# Analog.net
KiCad netlist of a schematic drawn in Altium Designer
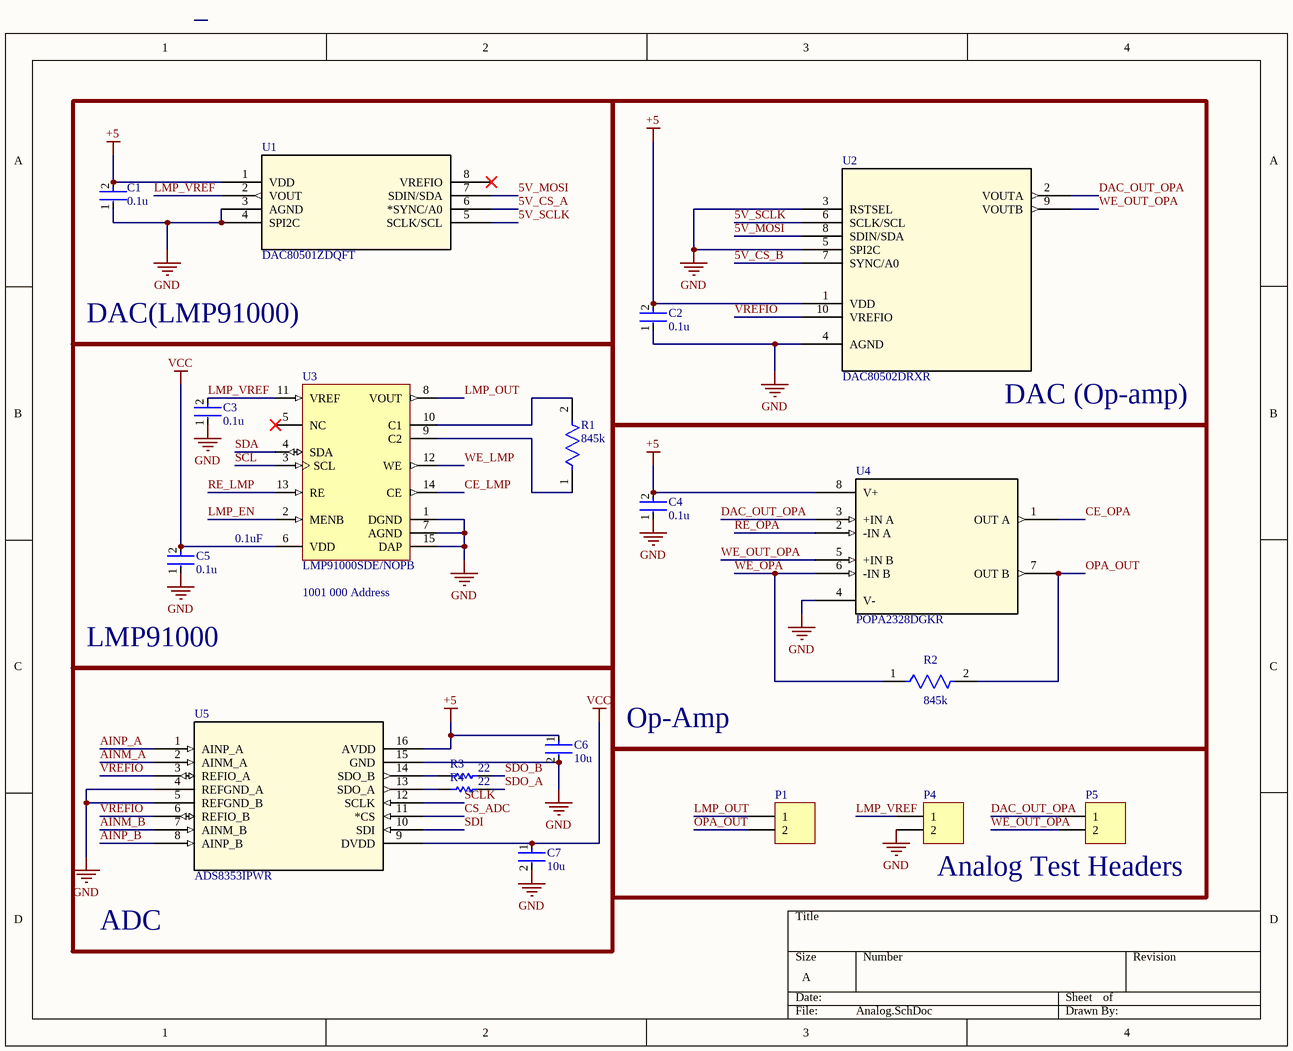
[diagram p0: Analog.SchDoc]

(export (version "E")
  (design (tool "Eeschema 10.0.6"))
  (components
    (comp (ref "C1")
      (value "0.1u")
      (footprint "FP-GCJ188-0_2-IPC_C")
      (description "Cap Ceramic 0.1uF 50V X7R 10% Pad SMD 0603 Soft Termination +125°C Automotive T/R")
      (fields (field (name "TOLERANCE") "10%"))
      (libsource (lib "Altium Content Vault") (part "f23184f103b6ebe33a8c269c53dcba6"))
    )
    (comp (ref "C2")
      (value "0.1u")
      (footprint "FP-GCJ188-0_2-IPC_C")
      (description "Cap Ceramic 0.1uF 50V X7R 10% Pad SMD 0603 Soft Termination +125°C Automotive T/R")
      (fields (field (name "TOLERANCE") "10%"))
      (libsource (lib "Altium Content Vault") (part "f23184f103b6ebe33a8c269c53dcba6"))
    )
    (comp (ref "C3")
      (value "0.1u")
      (footprint "FP-GCJ188-0_2-IPC_C")
      (description "Cap Ceramic 0.1uF 50V X7R 10% Pad SMD 0603 Soft Termination +125°C Automotive T/R")
      (fields (field (name "TOLERANCE") "10%"))
      (libsource (lib "Altium Content Vault") (part "f23184f103b6ebe33a8c269c53dcba6"))
    )
    (comp (ref "C4")
      (value "0.1u")
      (footprint "FP-GCJ188-0_2-IPC_C")
      (description "Cap Ceramic 0.1uF 50V X7R 10% Pad SMD 0603 Soft Termination +125°C Automotive T/R")
      (fields (field (name "TOLERANCE") "10%"))
      (libsource (lib "Altium Content Vault") (part "f23184f103b6ebe33a8c269c53dcba6"))
    )
    (comp (ref "C5")
      (value "0.1u")
      (footprint "FP-GCJ188-0_2-IPC_C")
      (description "Cap Ceramic 0.1uF 50V X7R 10% Pad SMD 0603 Soft Termination +125°C Automotive T/R")
      (fields (field (name "TOLERANCE") "10%"))
      (libsource (lib "Altium Content Vault") (part "f23184f103b6ebe33a8c269c53dcba6"))
    )
    (comp (ref "C6")
      (value "10u")
      (footprint "FP-CL21-IPC_C")
      (description "CL21 Series 0805 10uF 6.3V ±10% Tolerance X7R Multilayer Ceramic Chip Capacitor")
      (fields (field (name "TOLERANCE") "10%") (field (name "VOLTAGE") "6.3V"))
      (libsource (lib "Altium Content Vault") (part "b4654b650e69147ec39a6b967a45e02"))
    )
    (comp (ref "C7")
      (value "10u")
      (footprint "FP-CL21-IPC_C")
      (description "CL21 Series 0805 10uF 6.3V ±10% Tolerance X7R Multilayer Ceramic Chip Capacitor")
      (fields (field (name "TOLERANCE") "10%") (field (name "VOLTAGE") "6.3V"))
      (libsource (lib "Altium Content Vault") (part "b4654b650e69147ec39a6b967a45e02"))
    )
    (comp (ref "P1")
      (value "Header 2")
      (footprint "My_1X02")
      (description "Header, 2-Pin")
      (fields (field (name "ASID PART NUMBER") "Header 2-AS"))
      (libsource (lib "Mylib+Rev+4 (1)") (part "Header 2"))
    )
    (comp (ref "P4")
      (value "Header 2")
      (footprint "My_1X02")
      (description "Header, 2-Pin")
      (fields (field (name "ASID PART NUMBER") "Header 2-AS"))
      (libsource (lib "Mylib+Rev+4 (1)") (part "Header 2"))
    )
    (comp (ref "P5")
      (value "Header 2")
      (footprint "My_1X02")
      (description "Header, 2-Pin")
      (fields (field (name "ASID PART NUMBER") "Header 2-AS"))
      (libsource (lib "Mylib+Rev+4 (1)") (part "Header 2"))
    )
    (comp (ref "R1")
      (value "845k")
      (footprint "FP-CR0603-IPC_B")
      (description "Thick Film Chip Resistors 0603 845kΩ 0.1W 1% 100ppm/°C")
      (fields (field (name "TOLERANCE") "1%"))
      (libsource (lib "Altium Content Vault") (part "1029c3af85768c4190bb7ad29bc67b5"))
    )
    (comp (ref "R2")
      (value "845k")
      (footprint "FP-CR0603-IPC_B")
      (description "Thick Film Chip Resistors 0603 845kΩ 0.1W 1% 100ppm/°C")
      (fields (field (name "TOLERANCE") "1%"))
      (libsource (lib "Altium Content Vault") (part "1029c3af85768c4190bb7ad29bc67b5"))
    )
    (comp (ref "R3")
      (value "22")
      (footprint "RESC1608X55X25LL10T15")
      (fields (field (name "MANUFACTURER") "Yageo") (field (name "PART NUMBER") "RC0603FR-1022RL"))
      (libsource (lib "Altium Content Vault") (part "RES"))
    )
    (comp (ref "R4")
      (value "22")
      (footprint "RESC1608X55X25LL10T15")
      (fields (field (name "MANUFACTURER") "Yageo") (field (name "PART NUMBER") "RC0603FR-1022RL"))
      (libsource (lib "Altium Content Vault") (part "RES"))
    )
    (comp (ref "U1")
      (value "DAC80501ZDQFT")
      (footprint "WSON8_2P1X2P1_TEX")
      (description "True 16-bit, 1-ch, SPI/I2C, voltage-output DAC in WSON package with precision internal reference")
      (libsource (lib "DAC80501ZDQFT") (part "DAC80501ZDQFT"))
    )
    (comp (ref "U2")
      (value "DAC80502DRXR")
      (footprint "SON_02DRXR_TEX")
      (description "Dual-channel, 1-LSB INL, 16-bit, SPI voltage-output digital-to-analog converter (DAC)")
      (libsource (lib "DAC80502DRXR") (part "DAC80502DRXR"))
    )
    (comp (ref "U3")
      (value "LMP91000SDE/NOPB")
      (footprint "NHL0014B_V")
      (description "Configurable AFE Potentiostat for Low-Power Chemical Sensing Applications, 14-pin LLP, 250 Reel")
      (fields (field (name "MANUFACTURER") "Texas Instruments"))
      (libsource (lib "Altium Content Vault") (part "SEN-ELECHEM-LMP91000-15"))
    )
    (comp (ref "U4")
      (value "POPA2328DGKR")
      (footprint "SO8_DGK_TEX")
      (description "Dual-channel, precision, 50-µV offset voltage, 40-MHz wide-bandwidth RRIO CMOS op amp")
      (libsource (lib "POPA2328DGKR") (part "POPA2328DGKR"))
    )
    (comp (ref "U5")
      (value "ADS8353IPWR")
      (footprint "PW16_TEX")
      (description "16-bit 600-kSPS 2-channel simultaneous-sampling SAR ADC with single-ended inputs")
      (libsource (lib "ADS8353IPWR") (part "ADS8353IPWR"))
    )
  )
  (nets
    (net (code "1") (name "+5") (class "Default")
      (node (ref "C1") (pin "2") (pinfunction "2_2") (pintype "passive"))
      (node (ref "C2") (pin "2") (pinfunction "2_2") (pintype "passive"))
      (node (ref "C4") (pin "2") (pinfunction "2_2") (pintype "passive"))
      (node (ref "C6") (pin "1") (pinfunction "1_1") (pintype "passive"))
      (node (ref "U1") (pin "1") (pinfunction "VDD_1") (pintype "power_in"))
      (node (ref "U2") (pin "1") (pinfunction "VDD_1") (pintype "power_in"))
      (node (ref "U4") (pin "8") (pinfunction "V+_8") (pintype "power_in"))
      (node (ref "U5") (pin "16") (pinfunction "AVDD_16") (pintype "power_in"))
    )
    (net (code "2") (name "/5V_CS_A") (class "Default")
      (node (ref "U1") (pin "6") (pinfunction "*SYNC/A0_6") (pintype "passive"))
    )
    (net (code "3") (name "/5V_CS_B") (class "Default")
      (node (ref "U2") (pin "7") (pinfunction "SYNC/A0_7") (pintype "passive"))
    )
    (net (code "4") (name "/5V_MOSI") (class "Default")
      (node (ref "U1") (pin "7") (pinfunction "SDIN/SDA_7") (pintype "passive"))
      (node (ref "U2") (pin "8") (pinfunction "SDIN/SDA_8") (pintype "passive"))
    )
    (net (code "5") (name "/5V_SCLK") (class "Default")
      (node (ref "U1") (pin "5") (pinfunction "SCLK/SCL_5") (pintype "passive"))
      (node (ref "U2") (pin "6") (pinfunction "SCLK/SCL_6") (pintype "passive"))
    )
    (net (code "6") (name "/AINM_A") (class "Default")
      (node (ref "U5") (pin "2") (pinfunction "AINM_A_2") (pintype "input"))
    )
    (net (code "7") (name "/AINM_B") (class "Default")
      (node (ref "U5") (pin "7") (pinfunction "AINM_B_7") (pintype "input"))
    )
    (net (code "8") (name "/AINP_A") (class "Default")
      (node (ref "U5") (pin "1") (pinfunction "AINP_A_1") (pintype "input"))
    )
    (net (code "9") (name "/AINP_B") (class "Default")
      (node (ref "U5") (pin "8") (pinfunction "AINP_B_8") (pintype "input"))
    )
    (net (code "10") (name "/CE_LMP") (class "Default")
      (node (ref "U3") (pin "14") (pinfunction "CE_14") (pintype "output"))
    )
    (net (code "11") (name "/CE_OPA") (class "Default")
      (node (ref "U4") (pin "1") (pinfunction "OUT_A_1") (pintype "output"))
    )
    (net (code "12") (name "/CS_ADC") (class "Default")
      (node (ref "U5") (pin "11") (pinfunction "*CS_11") (pintype "input"))
    )
    (net (code "13") (name "/DAC_OUT_OPA") (class "Default")
      (node (ref "P5") (pin "1") (pinfunction "1_1") (pintype "passive"))
      (node (ref "U2") (pin "2") (pinfunction "VOUTA_2") (pintype "output"))
      (node (ref "U4") (pin "3") (pinfunction "+IN_A_3") (pintype "input"))
    )
    (net (code "14") (name "/LMP_EN") (class "Default")
      (node (ref "U3") (pin "2") (pinfunction "MENB_2") (pintype "input"))
    )
    (net (code "15") (name "/LMP_OUT") (class "Default")
      (node (ref "P1") (pin "1") (pinfunction "1_1") (pintype "passive"))
      (node (ref "U3") (pin "8") (pinfunction "VOUT_8") (pintype "output"))
    )
    (net (code "16") (name "/LMP_VREF") (class "Default")
      (node (ref "C3") (pin "2") (pinfunction "2_2") (pintype "passive"))
      (node (ref "P4") (pin "1") (pinfunction "1_1") (pintype "passive"))
      (node (ref "U1") (pin "2") (pinfunction "VOUT_2") (pintype "output"))
      (node (ref "U3") (pin "11") (pinfunction "VREF_11") (pintype "input"))
    )
    (net (code "17") (name "/OPA_OUT") (class "Default")
      (node (ref "P1") (pin "2") (pinfunction "2_2") (pintype "passive"))
      (node (ref "R2") (pin "2") (pinfunction "2_2") (pintype "passive"))
      (node (ref "U4") (pin "7") (pinfunction "OUT_B_7") (pintype "output"))
    )
    (net (code "18") (name "/RE_LMP") (class "Default")
      (node (ref "U3") (pin "13") (pinfunction "RE_13") (pintype "input"))
    )
    (net (code "19") (name "/RE_OPA") (class "Default")
      (node (ref "U4") (pin "2") (pinfunction "-IN_A_2") (pintype "input"))
    )
    (net (code "20") (name "/SCL") (class "Default")
      (node (ref "U3") (pin "3") (pinfunction "SCL_3") (pintype "input"))
    )
    (net (code "21") (name "/SCLK") (class "Default")
      (node (ref "U5") (pin "12") (pinfunction "SCLK_12") (pintype "input"))
    )
    (net (code "22") (name "/SDA") (class "Default")
      (node (ref "U3") (pin "4") (pinfunction "SDA_4") (pintype "bidirectional"))
    )
    (net (code "23") (name "/SDI") (class "Default")
      (node (ref "U5") (pin "10") (pinfunction "SDI_10") (pintype "input"))
    )
    (net (code "24") (name "/SDO_A") (class "Default")
      (node (ref "R4") (pin "2") (pinfunction "2_2") (pintype "passive"))
    )
    (net (code "25") (name "/SDO_B") (class "Default")
      (node (ref "R3") (pin "2") (pinfunction "2_2") (pintype "passive"))
    )
    (net (code "26") (name "/VREFIO") (class "Default")
      (node (ref "U2") (pin "10") (pinfunction "VREFIO_10") (pintype "power_in"))
      (node (ref "U5") (pin "3") (pinfunction "REFIO_A_3") (pintype "bidirectional"))
      (node (ref "U5") (pin "6") (pinfunction "REFIO_B_6") (pintype "bidirectional"))
    )
    (net (code "27") (name "/WE_LMP") (class "Default")
      (node (ref "U3") (pin "12") (pinfunction "WE_12") (pintype "output"))
    )
    (net (code "28") (name "/WE_OPA") (class "Default")
      (node (ref "R2") (pin "1") (pinfunction "1_1") (pintype "passive"))
      (node (ref "U4") (pin "6") (pinfunction "-IN_B_6") (pintype "input"))
    )
    (net (code "29") (name "/WE_OUT_OPA") (class "Default")
      (node (ref "P5") (pin "2") (pinfunction "2_2") (pintype "passive"))
      (node (ref "U2") (pin "9") (pinfunction "VOUTB_9") (pintype "output"))
      (node (ref "U4") (pin "5") (pinfunction "+IN_B_5") (pintype "input"))
    )
    (net (code "30") (name "GND") (class "Default")
      (node (ref "C1") (pin "1") (pinfunction "1_1") (pintype "passive"))
      (node (ref "C2") (pin "1") (pinfunction "1_1") (pintype "passive"))
      (node (ref "C3") (pin "1") (pinfunction "1_1") (pintype "passive"))
      (node (ref "C4") (pin "1") (pinfunction "1_1") (pintype "passive"))
      (node (ref "C5") (pin "1") (pinfunction "1_1") (pintype "passive"))
      (node (ref "C6") (pin "2") (pinfunction "2_2") (pintype "passive"))
      (node (ref "C7") (pin "2") (pinfunction "2_2") (pintype "passive"))
      (node (ref "P4") (pin "2") (pinfunction "2_2") (pintype "passive"))
      (node (ref "U1") (pin "3") (pinfunction "AGND_3") (pintype "power_in"))
      (node (ref "U1") (pin "4") (pinfunction "SPI2C_4") (pintype "passive"))
      (node (ref "U2") (pin "3") (pinfunction "RSTSEL_3") (pintype "passive"))
      (node (ref "U2") (pin "4") (pinfunction "AGND_4") (pintype "power_in"))
      (node (ref "U2") (pin "5") (pinfunction "SPI2C_5") (pintype "passive"))
      (node (ref "U3") (pin "1") (pinfunction "DGND_1") (pintype "power_in"))
      (node (ref "U3") (pin "15") (pinfunction "DAP_15") (pintype "power_in"))
      (node (ref "U3") (pin "7") (pinfunction "AGND_7") (pintype "power_in"))
      (node (ref "U4") (pin "4") (pinfunction "V-_4") (pintype "power_in"))
      (node (ref "U5") (pin "15") (pinfunction "GND_15") (pintype "power_in"))
      (node (ref "U5") (pin "4") (pinfunction "REFGND_A_4") (pintype "power_in"))
      (node (ref "U5") (pin "5") (pinfunction "REFGND_B_5") (pintype "power_in"))
    )
    (net (code "31") (name "Net-(U3-C1)") (class "Default")
      (node (ref "R1") (pin "2") (pinfunction "2_2") (pintype "passive"))
      (node (ref "U3") (pin "10") (pinfunction "C1_10") (pintype "passive"))
    )
    (net (code "32") (name "Net-(U3-C2)") (class "Default")
      (node (ref "R1") (pin "1") (pinfunction "1_1") (pintype "passive"))
      (node (ref "U3") (pin "9") (pinfunction "C2_9") (pintype "passive"))
    )
    (net (code "33") (name "Net-(U5-SDO_A)") (class "Default")
      (node (ref "R4") (pin "1") (pinfunction "1_1") (pintype "passive"))
      (node (ref "U5") (pin "13") (pinfunction "SDO_A_13") (pintype "output"))
    )
    (net (code "34") (name "Net-(U5-SDO_B)") (class "Default")
      (node (ref "R3") (pin "1") (pinfunction "1_1") (pintype "passive"))
      (node (ref "U5") (pin "14") (pinfunction "SDO_B_14") (pintype "output"))
    )
    (net (code "35") (name "VCC") (class "Default")
      (node (ref "C5") (pin "2") (pinfunction "2_2") (pintype "passive"))
      (node (ref "C7") (pin "1") (pinfunction "1_1") (pintype "passive"))
      (node (ref "U3") (pin "6") (pinfunction "VDD_6") (pintype "power_in"))
      (node (ref "U5") (pin "9") (pinfunction "DVDD_9") (pintype "power_in"))
    )
    (net (code "36") (name "unconnected-(U1-VREFIO-Pad8)") (class "Default")
      (node (ref "U1") (pin "8") (pinfunction "VREFIO_8") (pintype "power_in+no_connect"))
    )
    (net (code "37") (name "unconnected-(U3-NC-Pad5)") (class "Default")
      (node (ref "U3") (pin "5") (pinfunction "NC_5") (pintype "passive+no_connect"))
    )
  )
)
